# gocupi_v1_1.net
KiCad netlist of a schematic drawn in EAGLE
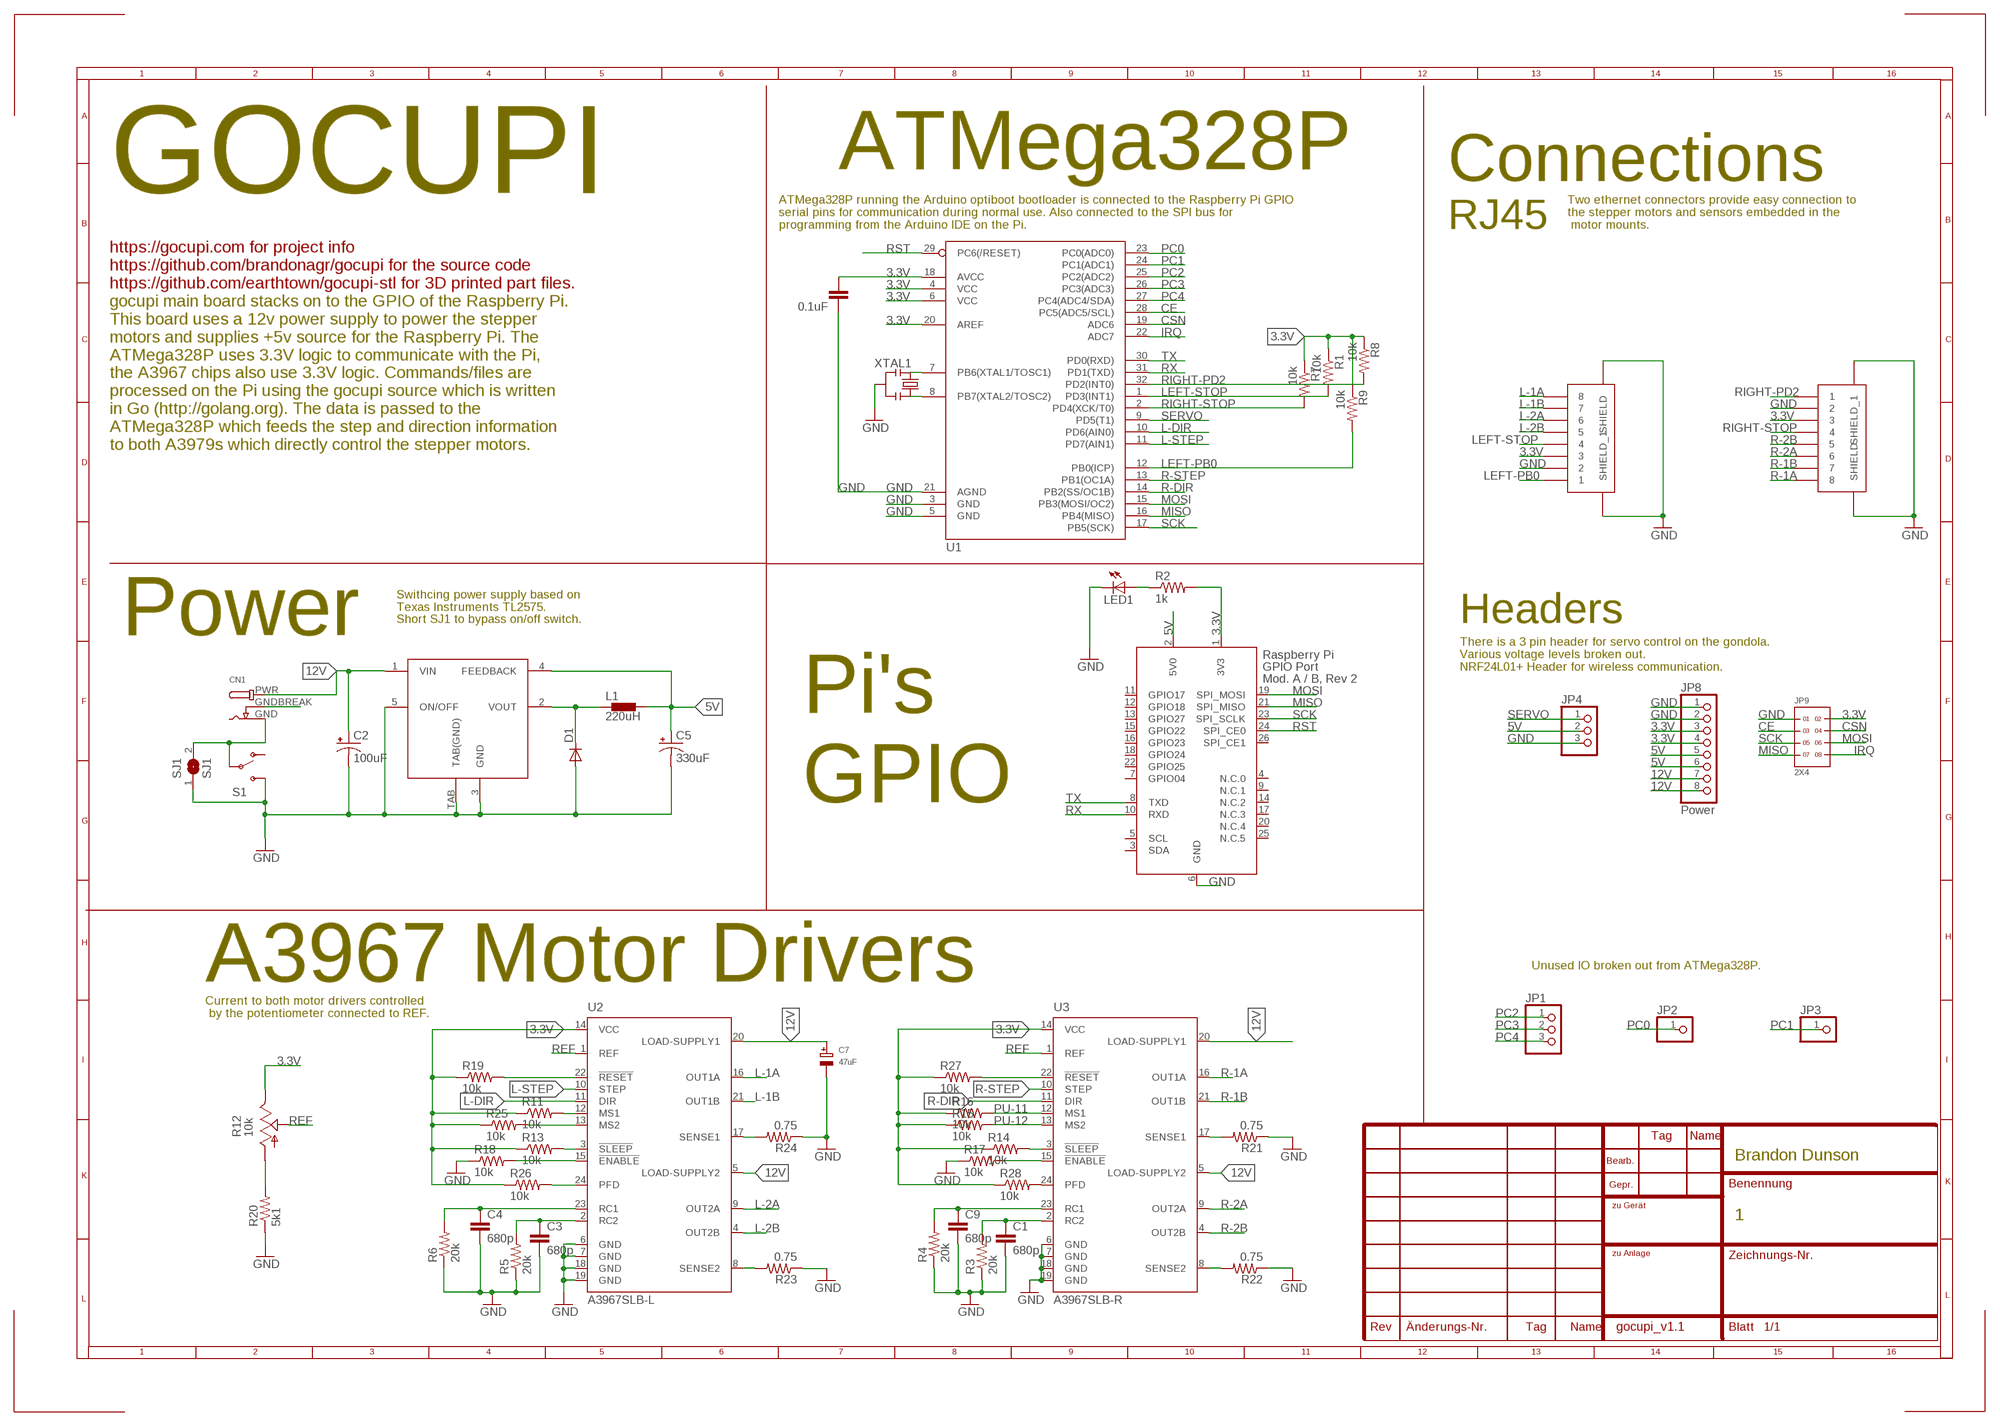
[diagram p0: schematic, sheet 1]

(export (version "E")
  (design (tool "Eeschema 10.0.6"))
  (components
    (comp (ref "C1")
      (value "680p")
      (footprint "eagle-import:0805")
      (libsource (lib "eagle-import") (part "CAP0805"))
    )
    (comp (ref "C2")
      (value "100uF")
      (footprint "eagle-import:PANASONIC_D")
      (libsource (lib "eagle-import") (part "CPOL-USD"))
    )
    (comp (ref "C3")
      (value "680p")
      (footprint "eagle-import:0805")
      (libsource (lib "eagle-import") (part "CAP0805"))
    )
    (comp (ref "C4")
      (value "680p")
      (footprint "eagle-import:0805")
      (libsource (lib "eagle-import") (part "CAP0805"))
    )
    (comp (ref "C5")
      (value "330uF")
      (footprint "eagle-import:PANASONIC_F")
      (libsource (lib "eagle-import") (part "CPOL-USF"))
    )
    (comp (ref "C7")
      (value "47uF")
      (footprint "eagle-import:PANASONIC_C")
      (libsource (lib "eagle-import") (part "CAP_ELECTROLYTICPANASONIC_C"))
    )
    (comp (ref "C8")
      (value "0.1uF")
      (footprint "eagle-import:0805")
      (libsource (lib "eagle-import") (part "CAP0805"))
    )
    (comp (ref "C9")
      (value "680p")
      (footprint "eagle-import:0805")
      (libsource (lib "eagle-import") (part "CAP0805"))
    )
    (comp (ref "CN1")
      (value "DCBARRELSMT_CORRECT")
      (footprint "eagle-import:DCJACK_2MM_SMT")
      (libsource (lib "eagle-import") (part "DCBARRELSMT_CORRECT"))
    )
    (comp (ref "D1")
      (value "DIODE-SOD-123")
      (footprint "eagle-import:SOD-123")
      (libsource (lib "eagle-import") (part "DIODE-SOD-123"))
    )
    (comp (ref "JP1")
      (value "PINHD-1X3CB")
      (footprint "eagle-import:1X03-CLEANBIG")
      (libsource (lib "eagle-import") (part "PINHD-1X3CB"))
    )
    (comp (ref "JP2")
      (value "PINHD-1X1CB")
      (footprint "eagle-import:1X01-CLEANBIG")
      (libsource (lib "eagle-import") (part "PINHD-1X1CB"))
    )
    (comp (ref "JP3")
      (value "PINHD-1X1CB")
      (footprint "eagle-import:1X01-CLEANBIG")
      (libsource (lib "eagle-import") (part "PINHD-1X1CB"))
    )
    (comp (ref "JP4")
      (value "PINHD-1X3")
      (footprint "eagle-import:1X03")
      (libsource (lib "eagle-import") (part "PINHD-1X3"))
    )
    (comp (ref "JP8")
      (value "Power")
      (footprint "eagle-import:1X08-CLEANBIG")
      (libsource (lib "eagle-import") (part "PINHD-1X8CLEANBIG"))
    )
    (comp (ref "JP9")
      (value "2X4")
      (footprint "eagle-import:2X4")
      (libsource (lib "eagle-import") (part "2X4"))
    )
    (comp (ref "L1")
      (value "220uH")
      (footprint "eagle-import:SDR1305")
      (libsource (lib "eagle-import") (part "SDR1305"))
    )
    (comp (ref "LED1")
      (value "LEDCHIPLED_0805")
      (footprint "eagle-import:CHIPLED_0805")
      (libsource (lib "eagle-import") (part "LEDCHIPLED_0805"))
    )
    (comp (ref "R1")
      (value "10k")
      (footprint "eagle-import:0805")
      (libsource (lib "eagle-import") (part "SparkFun-Resistors_RESISTOR0805-RES"))
    )
    (comp (ref "R2")
      (value "1k")
      (footprint "eagle-import:0805")
      (libsource (lib "eagle-import") (part "SparkFun-Resistors_RESISTOR0805-RES"))
    )
    (comp (ref "R3")
      (value "20k")
      (footprint "eagle-import:0805")
      (libsource (lib "eagle-import") (part "SparkFun-Resistors_RESISTOR0805-RES"))
    )
    (comp (ref "R4")
      (value "20k")
      (footprint "eagle-import:0805")
      (libsource (lib "eagle-import") (part "SparkFun-Resistors_RESISTOR0805-RES"))
    )
    (comp (ref "R5")
      (value "20k")
      (footprint "eagle-import:0805")
      (libsource (lib "eagle-import") (part "SparkFun-Resistors_RESISTOR0805-RES"))
    )
    (comp (ref "R6")
      (value "20k")
      (footprint "eagle-import:0805")
      (libsource (lib "eagle-import") (part "SparkFun-Resistors_RESISTOR0805-RES"))
    )
    (comp (ref "R7")
      (value "10k")
      (footprint "eagle-import:0805")
      (libsource (lib "eagle-import") (part "SparkFun-Resistors_RESISTOR0805-RES"))
    )
    (comp (ref "R8")
      (value "10k")
      (footprint "eagle-import:0805")
      (libsource (lib "eagle-import") (part "SparkFun-Resistors_RESISTOR0805-RES"))
    )
    (comp (ref "R9")
      (value "10k")
      (footprint "eagle-import:0805")
      (libsource (lib "eagle-import") (part "SparkFun-Resistors_RESISTOR0805-RES"))
    )
    (comp (ref "R11")
      (value "10k")
      (footprint "eagle-import:0805")
      (libsource (lib "eagle-import") (part "SparkFun-Resistors_RESISTOR0805-RES"))
    )
    (comp (ref "R12")
      (value "10k")
      (footprint "eagle-import:SM-42_43A")
      (libsource (lib "eagle-import") (part "TRIM_US-SM-42/43A"))
    )
    (comp (ref "R13")
      (value "10k")
      (footprint "eagle-import:0805")
      (libsource (lib "eagle-import") (part "SparkFun-Resistors_RESISTOR0805-RES"))
    )
    (comp (ref "R14")
      (value "10k")
      (footprint "eagle-import:0805")
      (libsource (lib "eagle-import") (part "SparkFun-Resistors_RESISTOR0805-RES"))
    )
    (comp (ref "R15")
      (value "10k")
      (footprint "eagle-import:0805")
      (libsource (lib "eagle-import") (part "SparkFun-Resistors_RESISTOR0805-RES"))
    )
    (comp (ref "R16")
      (value "10k")
      (footprint "eagle-import:0805")
      (libsource (lib "eagle-import") (part "SparkFun-Resistors_RESISTOR0805-RES"))
    )
    (comp (ref "R17")
      (value "10k")
      (footprint "eagle-import:0805")
      (libsource (lib "eagle-import") (part "SparkFun-Resistors_RESISTOR0805-RES"))
    )
    (comp (ref "R18")
      (value "10k")
      (footprint "eagle-import:0805")
      (libsource (lib "eagle-import") (part "SparkFun-Resistors_RESISTOR0805-RES"))
    )
    (comp (ref "R19")
      (value "10k")
      (footprint "eagle-import:0805")
      (libsource (lib "eagle-import") (part "SparkFun-Resistors_RESISTOR0805-RES"))
    )
    (comp (ref "R20")
      (value "5k1")
      (footprint "eagle-import:0805")
      (libsource (lib "eagle-import") (part "SparkFun-Resistors_RESISTOR0805-RES"))
    )
    (comp (ref "R21")
      (value "0.75")
      (footprint "eagle-import:0805")
      (libsource (lib "eagle-import") (part "SparkFun-Resistors_RESISTOR0805-RES"))
    )
    (comp (ref "R22")
      (value "0.75")
      (footprint "eagle-import:0805")
      (libsource (lib "eagle-import") (part "SparkFun-Resistors_RESISTOR0805-RES"))
    )
    (comp (ref "R23")
      (value "0.75")
      (footprint "eagle-import:0805")
      (libsource (lib "eagle-import") (part "SparkFun-Resistors_RESISTOR0805-RES"))
    )
    (comp (ref "R24")
      (value "0.75")
      (footprint "eagle-import:0805")
      (libsource (lib "eagle-import") (part "SparkFun-Resistors_RESISTOR0805-RES"))
    )
    (comp (ref "R25")
      (value "10k")
      (footprint "eagle-import:0805")
      (libsource (lib "eagle-import") (part "RESISTOR0805-RES"))
    )
    (comp (ref "R26")
      (value "10k")
      (footprint "eagle-import:0805")
      (libsource (lib "eagle-import") (part "SparkFun-Resistors_RESISTOR0805-RES"))
    )
    (comp (ref "R27")
      (value "10k")
      (footprint "eagle-import:0805")
      (libsource (lib "eagle-import") (part "SparkFun-Resistors_RESISTOR0805-RES"))
    )
    (comp (ref "R28")
      (value "10k")
      (footprint "eagle-import:0805")
      (libsource (lib "eagle-import") (part "SparkFun-Resistors_RESISTOR0805-RES"))
    )
    (comp (ref "RJ45-L")
      (value "RJ45_SMD")
      (footprint "eagle-import:RJ45_SMD")
      (libsource (lib "eagle-import") (part "RJ45_SMD"))
    )
    (comp (ref "RJ45-R")
      (value "RJ45_SMD")
      (footprint "eagle-import:RJ45_SMD")
      (libsource (lib "eagle-import") (part "RJ45_SMD"))
    )
    (comp (ref "S1")
      (value "SWITCH-SPST-SMD-A")
      (footprint "eagle-import:SWITCH-SPST-SMD-A")
      (libsource (lib "eagle-import") (part "SWITCH-SPST-SMD-A"))
    )
    (comp (ref "SJ1")
      (value "SJ1")
      (footprint "eagle-import:SJ")
      (libsource (lib "eagle-import") (part "SJ"))
    )
    (comp (ref "U1")
      (value "ATMEGA328_SMT")
      (footprint "eagle-import:TQFP32-08")
      (libsource (lib "eagle-import") (part "ATMEGA328_SMT"))
    )
    (comp (ref "U2")
      (value "A3967SLB-L")
      (footprint "eagle-import:SO24W")
      (fields (field (name "MF") "ALLEGRO MICROSYSTEMS, INC.") (field (name "MPN") "A3967SLB-T"))
      (libsource (lib "eagle-import") (part "A3967SLB"))
    )
    (comp (ref "U3")
      (value "A3967SLB-R")
      (footprint "eagle-import:SO24W")
      (fields (field (name "MF") "ALLEGRO MICROSYSTEMS, INC.") (field (name "MPN") "A3967SLB-T"))
      (libsource (lib "eagle-import") (part "A3967SLB"))
    )
    (comp (ref "U4")
      (value "TL2575")
      (footprint "eagle-import:TO263_5")
      (libsource (lib "eagle-import") (part "TL2575"))
    )
    (comp (ref "X1")
      (value "RASPI_BOARD_AB_E2P")
      (footprint "eagle-import:RASPI_BOARD_AB_EDGES_2DRILL_PAD")
      (libsource (lib "eagle-import") (part "RASPI_BOARD_AB_E2P"))
    )
    (comp (ref "XTAL1")
      (value "10MHz")
      (footprint "eagle-import:RESONATOR-SMD")
      (libsource (lib "eagle-import") (part "RESONATORSMD"))
    )
  )
  (nets
    (net (code "1") (name "/CE") (class "Default")
      (node (ref "JP9") (pin "3") (pinfunction "3_3") (pintype "bidirectional"))
      (node (ref "U1") (pin "28") (pinfunction "PC5(ADC5/SCL)_28") (pintype "bidirectional"))
    )
    (net (code "2") (name "/CSN") (class "Default")
      (node (ref "JP9") (pin "4") (pinfunction "4_4") (pintype "bidirectional"))
      (node (ref "U1") (pin "19") (pinfunction "ADC6_19") (pintype "bidirectional"))
    )
    (net (code "3") (name "/IRQ") (class "Default")
      (node (ref "JP9") (pin "8") (pinfunction "8_8") (pintype "bidirectional"))
      (node (ref "U1") (pin "22") (pinfunction "ADC7_22") (pintype "bidirectional"))
    )
    (net (code "4") (name "/L-1A") (class "Default")
      (node (ref "RJ45-L") (pin "P$8") (pinfunction "8_P$8") (pintype "bidirectional"))
      (node (ref "U2") (pin "16") (pinfunction "OUT1A_16") (pintype "output"))
    )
    (net (code "5") (name "/L-1B") (class "Default")
      (node (ref "RJ45-L") (pin "P$7") (pinfunction "7_P$7") (pintype "bidirectional"))
      (node (ref "U2") (pin "21") (pinfunction "OUT1B_21") (pintype "output"))
    )
    (net (code "6") (name "/L-2A") (class "Default")
      (node (ref "RJ45-L") (pin "P$6") (pinfunction "6_P$6") (pintype "bidirectional"))
      (node (ref "U2") (pin "9") (pinfunction "OUT2A_9") (pintype "output"))
    )
    (net (code "7") (name "/L-2B") (class "Default")
      (node (ref "RJ45-L") (pin "P$5") (pinfunction "5_P$5") (pintype "bidirectional"))
      (node (ref "U2") (pin "4") (pinfunction "OUT2B_4") (pintype "output"))
    )
    (net (code "8") (name "/LEFT-PB0") (class "Default")
      (node (ref "R9") (pin "2") (pinfunction "2_2") (pintype "passive"))
      (node (ref "RJ45-L") (pin "P$1") (pinfunction "1_P$1") (pintype "bidirectional"))
      (node (ref "U1") (pin "12") (pinfunction "PB0(ICP)_12") (pintype "bidirectional"))
    )
    (net (code "9") (name "/LEFT-STOP") (class "Default")
      (node (ref "R1") (pin "2") (pinfunction "2_2") (pintype "passive"))
      (node (ref "RJ45-L") (pin "P$4") (pinfunction "4_P$4") (pintype "bidirectional"))
      (node (ref "U1") (pin "1") (pinfunction "PD3(INT1)_1") (pintype "bidirectional"))
    )
    (net (code "10") (name "/MISO") (class "Default")
      (node (ref "JP9") (pin "7") (pinfunction "7_7") (pintype "bidirectional"))
      (node (ref "U1") (pin "16") (pinfunction "PB4(MISO)_16") (pintype "bidirectional"))
      (node (ref "X1") (pin "21") (pinfunction "SPI_MISO_21") (pintype "bidirectional"))
    )
    (net (code "11") (name "/MOSI") (class "Default")
      (node (ref "JP9") (pin "6") (pinfunction "6_6") (pintype "bidirectional"))
      (node (ref "U1") (pin "15") (pinfunction "PB3(MOSI/OC2)_15") (pintype "bidirectional"))
      (node (ref "X1") (pin "19") (pinfunction "SPI_MOSI_19") (pintype "bidirectional"))
    )
    (net (code "12") (name "/PC0") (class "Default")
      (node (ref "JP2") (pin "1") (pinfunction "1_1") (pintype "passive"))
      (node (ref "U1") (pin "23") (pinfunction "PC0(ADC0)_23") (pintype "bidirectional"))
    )
    (net (code "13") (name "/PC1") (class "Default")
      (node (ref "JP3") (pin "1") (pinfunction "1_1") (pintype "passive"))
      (node (ref "U1") (pin "24") (pinfunction "PC1(ADC1)_24") (pintype "bidirectional"))
    )
    (net (code "14") (name "/PC2") (class "Default")
      (node (ref "JP1") (pin "1") (pinfunction "1_1") (pintype "passive"))
      (node (ref "U1") (pin "25") (pinfunction "PC2(ADC2)_25") (pintype "bidirectional"))
    )
    (net (code "15") (name "/PC3") (class "Default")
      (node (ref "JP1") (pin "2") (pinfunction "2_2") (pintype "passive"))
      (node (ref "U1") (pin "26") (pinfunction "PC3(ADC3)_26") (pintype "bidirectional"))
    )
    (net (code "16") (name "/PC4") (class "Default")
      (node (ref "JP1") (pin "3") (pinfunction "3_3") (pintype "passive"))
      (node (ref "U1") (pin "27") (pinfunction "PC4(ADC4/SDA)_27") (pintype "bidirectional"))
    )
    (net (code "17") (name "/PU-11") (class "Default")
      (node (ref "R16") (pin "2") (pinfunction "2_2") (pintype "passive"))
      (node (ref "U3") (pin "12") (pinfunction "MS1_12") (pintype "input"))
    )
    (net (code "18") (name "/PU-12") (class "Default")
      (node (ref "R15") (pin "2") (pinfunction "2_2") (pintype "passive"))
      (node (ref "U3") (pin "13") (pinfunction "MS2_13") (pintype "input"))
    )
    (net (code "19") (name "/R-1A") (class "Default")
      (node (ref "RJ45-R") (pin "P$8") (pinfunction "8_P$8") (pintype "bidirectional"))
      (node (ref "U3") (pin "16") (pinfunction "OUT1A_16") (pintype "output"))
    )
    (net (code "20") (name "/R-1B") (class "Default")
      (node (ref "RJ45-R") (pin "P$7") (pinfunction "7_P$7") (pintype "bidirectional"))
      (node (ref "U3") (pin "21") (pinfunction "OUT1B_21") (pintype "output"))
    )
    (net (code "21") (name "/R-2A") (class "Default")
      (node (ref "RJ45-R") (pin "P$6") (pinfunction "6_P$6") (pintype "bidirectional"))
      (node (ref "U3") (pin "9") (pinfunction "OUT2A_9") (pintype "output"))
    )
    (net (code "22") (name "/R-2B") (class "Default")
      (node (ref "RJ45-R") (pin "P$5") (pinfunction "5_P$5") (pintype "bidirectional"))
      (node (ref "U3") (pin "4") (pinfunction "OUT2B_4") (pintype "output"))
    )
    (net (code "23") (name "/REF") (class "Default")
      (node (ref "R12") (pin "2") (pinfunction "S_2") (pintype "passive"))
      (node (ref "U2") (pin "1") (pinfunction "REF_1") (pintype "input"))
      (node (ref "U3") (pin "1") (pinfunction "REF_1") (pintype "input"))
    )
    (net (code "24") (name "/RIGHT-PD2") (class "Default")
      (node (ref "R8") (pin "2") (pinfunction "2_2") (pintype "passive"))
      (node (ref "RJ45-R") (pin "P$1") (pinfunction "1_P$1") (pintype "bidirectional"))
      (node (ref "U1") (pin "32") (pinfunction "PD2(INT0)_32") (pintype "bidirectional"))
    )
    (net (code "25") (name "/RIGHT-STOP") (class "Default")
      (node (ref "R7") (pin "2") (pinfunction "2_2") (pintype "passive"))
      (node (ref "RJ45-R") (pin "P$4") (pinfunction "4_P$4") (pintype "bidirectional"))
      (node (ref "U1") (pin "2") (pinfunction "PD4(XCK/T0)_2") (pintype "bidirectional"))
    )
    (net (code "26") (name "/RST") (class "Default")
      (node (ref "U1") (pin "29") (pinfunction "PC6(/RESET)_29") (pintype "bidirectional"))
      (node (ref "X1") (pin "24") (pinfunction "SPI_CE0_24") (pintype "bidirectional"))
    )
    (net (code "27") (name "/RX") (class "Default")
      (node (ref "U1") (pin "31") (pinfunction "PD1(TXD)_31") (pintype "bidirectional"))
      (node (ref "X1") (pin "10") (pinfunction "RXD_10") (pintype "bidirectional"))
    )
    (net (code "28") (name "/SCK") (class "Default")
      (node (ref "JP9") (pin "5") (pinfunction "5_5") (pintype "bidirectional"))
      (node (ref "U1") (pin "17") (pinfunction "PB5(SCK)_17") (pintype "bidirectional"))
      (node (ref "X1") (pin "23") (pinfunction "SPI_SCLK_23") (pintype "bidirectional"))
    )
    (net (code "29") (name "/SERVO") (class "Default")
      (node (ref "JP4") (pin "1") (pinfunction "1_1") (pintype "passive"))
      (node (ref "U1") (pin "9") (pinfunction "PD5(T1)_9") (pintype "bidirectional"))
    )
    (net (code "30") (name "/TX") (class "Default")
      (node (ref "U1") (pin "30") (pinfunction "PD0(RXD)_30") (pintype "bidirectional"))
      (node (ref "X1") (pin "8") (pinfunction "TXD_8") (pintype "bidirectional"))
    )
    (net (code "31") (name "3.3V") (class "Default")
      (node (ref "C8") (pin "1") (pinfunction "1_1") (pintype "passive"))
      (node (ref "JP8") (pin "3") (pinfunction "3_3") (pintype "passive"))
      (node (ref "JP8") (pin "4") (pinfunction "4_4") (pintype "passive"))
      (node (ref "JP9") (pin "2") (pinfunction "2_2") (pintype "bidirectional"))
      (node (ref "R1") (pin "1") (pinfunction "1_1") (pintype "passive"))
      (node (ref "R11") (pin "1") (pinfunction "1_1") (pintype "passive"))
      (node (ref "R12") (pin "3") (pinfunction "E_3") (pintype "passive"))
      (node (ref "R13") (pin "1") (pinfunction "1_1") (pintype "passive"))
      (node (ref "R14") (pin "1") (pinfunction "1_1") (pintype "passive"))
      (node (ref "R15") (pin "1") (pinfunction "1_1") (pintype "passive"))
      (node (ref "R16") (pin "1") (pinfunction "1_1") (pintype "passive"))
      (node (ref "R19") (pin "1") (pinfunction "1_1") (pintype "passive"))
      (node (ref "R2") (pin "2") (pinfunction "2_2") (pintype "passive"))
      (node (ref "R25") (pin "1") (pinfunction "1_1") (pintype "passive"))
      (node (ref "R26") (pin "1") (pinfunction "1_1") (pintype "passive"))
      (node (ref "R27") (pin "1") (pinfunction "1_1") (pintype "passive"))
      (node (ref "R28") (pin "1") (pinfunction "1_1") (pintype "passive"))
      (node (ref "R7") (pin "1") (pinfunction "1_1") (pintype "passive"))
      (node (ref "R8") (pin "1") (pinfunction "1_1") (pintype "passive"))
      (node (ref "R9") (pin "1") (pinfunction "1_1") (pintype "passive"))
      (node (ref "RJ45-L") (pin "P$3") (pinfunction "3_P$3") (pintype "bidirectional"))
      (node (ref "RJ45-R") (pin "P$3") (pinfunction "3_P$3") (pintype "bidirectional"))
      (node (ref "U1") (pin "18") (pinfunction "AVCC_18") (pintype "bidirectional"))
      (node (ref "U1") (pin "20") (pinfunction "AREF_20") (pintype "bidirectional"))
      (node (ref "U1") (pin "4") (pinfunction "VCC_4") (pintype "bidirectional"))
      (node (ref "U1") (pin "6") (pinfunction "VCC_6") (pintype "bidirectional"))
      (node (ref "U2") (pin "14") (pinfunction "VCC_14") (pintype "power_in"))
      (node (ref "U3") (pin "14") (pinfunction "VCC_14") (pintype "power_in"))
      (node (ref "X1") (pin "1") (pinfunction "3V3_1") (pintype "power_in"))
    )
    (net (code "32") (name "5V") (class "Default")
      (node (ref "C5") (pin "+") (pinfunction "+_+") (pintype "passive"))
      (node (ref "JP4") (pin "2") (pinfunction "2_2") (pintype "passive"))
      (node (ref "JP8") (pin "5") (pinfunction "5_5") (pintype "passive"))
      (node (ref "JP8") (pin "6") (pinfunction "6_6") (pintype "passive"))
      (node (ref "L1") (pin "P$2") (pinfunction "2_P$2") (pintype "passive"))
      (node (ref "U4") (pin "4") (pinfunction "FEEDBACK_4") (pintype "input"))
      (node (ref "X1") (pin "2") (pinfunction "5V0_2") (pintype "power_in"))
    )
    (net (code "33") (name "12V") (class "Default")
      (node (ref "C2") (pin "+") (pinfunction "+_+") (pintype "passive"))
      (node (ref "C7") (pin "+") (pinfunction "+_+") (pintype "passive"))
      (node (ref "CN1") (pin "PWR") (pinfunction "PWR_PWR") (pintype "power_in"))
      (node (ref "JP8") (pin "7") (pinfunction "7_7") (pintype "passive"))
      (node (ref "JP8") (pin "8") (pinfunction "8_8") (pintype "passive"))
      (node (ref "U2") (pin "20") (pinfunction "LOAD-SUPPLY1_20") (pintype "input"))
      (node (ref "U2") (pin "5") (pinfunction "LOAD-SUPPLY2_5") (pintype "input"))
      (node (ref "U3") (pin "20") (pinfunction "LOAD-SUPPLY1_20") (pintype "input"))
      (node (ref "U3") (pin "5") (pinfunction "LOAD-SUPPLY2_5") (pintype "input"))
      (node (ref "U4") (pin "1") (pinfunction "VIN_1") (pintype "input"))
    )
    (net (code "34") (name "GND") (class "Default")
      (node (ref "C1") (pin "2") (pinfunction "2_2") (pintype "passive"))
      (node (ref "C2") (pin "-") (pinfunction "-_-") (pintype "passive"))
      (node (ref "C3") (pin "2") (pinfunction "2_2") (pintype "passive"))
      (node (ref "C4") (pin "2") (pinfunction "2_2") (pintype "passive"))
      (node (ref "C5") (pin "-") (pinfunction "-_-") (pintype "passive"))
      (node (ref "C7") (pin "-") (pinfunction "-_-") (pintype "passive"))
      (node (ref "C8") (pin "2") (pinfunction "2_2") (pintype "passive"))
      (node (ref "C9") (pin "2") (pinfunction "2_2") (pintype "passive"))
      (node (ref "D1") (pin "A") (pinfunction "A_A") (pintype "passive"))
      (node (ref "JP4") (pin "3") (pinfunction "3_3") (pintype "passive"))
      (node (ref "JP8") (pin "1") (pinfunction "1_1") (pintype "passive"))
      (node (ref "JP8") (pin "2") (pinfunction "2_2") (pintype "passive"))
      (node (ref "JP9") (pin "1") (pinfunction "1_1") (pintype "bidirectional"))
      (node (ref "LED1") (pin "C") (pinfunction "C_C") (pintype "passive"))
      (node (ref "R17") (pin "1") (pinfunction "1_1") (pintype "passive"))
      (node (ref "R18") (pin "1") (pinfunction "1_1") (pintype "passive"))
      (node (ref "R20") (pin "1") (pinfunction "1_1") (pintype "passive"))
      (node (ref "R21") (pin "1") (pinfunction "1_1") (pintype "passive"))
      (node (ref "R22") (pin "1") (pinfunction "1_1") (pintype "passive"))
      (node (ref "R23") (pin "1") (pinfunction "1_1") (pintype "passive"))
      (node (ref "R24") (pin "1") (pinfunction "1_1") (pintype "passive"))
      (node (ref "R3") (pin "1") (pinfunction "1_1") (pintype "passive"))
      (node (ref "R4") (pin "1") (pinfunction "1_1") (pintype "passive"))
      (node (ref "R5") (pin "1") (pinfunction "1_1") (pintype "passive"))
      (node (ref "R6") (pin "1") (pinfunction "1_1") (pintype "passive"))
      (node (ref "RJ45-L") (pin "P$2") (pinfunction "2_P$2") (pintype "bidirectional"))
      (node (ref "RJ45-L") (pin "P$SHIELD") (pinfunction "SHIELD_P$SHIELD") (pintype "bidirectional"))
      (node (ref "RJ45-L") (pin "P$SHIELD_1") (pinfunction "SHIELD_1_P$SHIELD_1") (pintype "bidirectional"))
      (node (ref "RJ45-R") (pin "P$2") (pinfunction "2_P$2") (pintype "bidirectional"))
      (node (ref "RJ45-R") (pin "P$SHIELD") (pinfunction "SHIELD_P$SHIELD") (pintype "bidirectional"))
      (node (ref "RJ45-R") (pin "P$SHIELD_1") (pinfunction "SHIELD_1_P$SHIELD_1") (pintype "bidirectional"))
      (node (ref "S1") (pin "3") (pinfunction "S_3") (pintype "passive"))
      (node (ref "SJ1") (pin "1") (pinfunction "1_1") (pintype "passive"))
      (node (ref "U1") (pin "21") (pinfunction "AGND_21") (pintype "bidirectional"))
      (node (ref "U1") (pin "3") (pinfunction "GND_3") (pintype "bidirectional"))
      (node (ref "U1") (pin "5") (pinfunction "GND_5") (pintype "bidirectional"))
      (node (ref "U2") (pin "18") (pinfunction "GND_18") (pintype "power_in"))
      (node (ref "U2") (pin "19") (pinfunction "GND_19") (pintype "power_in"))
      (node (ref "U2") (pin "6") (pinfunction "GND_6") (pintype "power_in"))
      (node (ref "U2") (pin "7") (pinfunction "GND_7") (pintype "power_in"))
      (node (ref "U3") (pin "18") (pinfunction "GND_18") (pintype "power_in"))
      (node (ref "U3") (pin "19") (pinfunction "GND_19") (pintype "power_in"))
      (node (ref "U3") (pin "6") (pinfunction "GND_6") (pintype "power_in"))
      (node (ref "U3") (pin "7") (pinfunction "GND_7") (pintype "power_in"))
      (node (ref "U4") (pin "3") (pinfunction "GND_3") (pintype "power_in"))
      (node (ref "U4") (pin "5") (pinfunction "ON/OFF_5") (pintype "bidirectional"))
      (node (ref "U4") (pin "TAB") (pinfunction "TAB(GND)_TAB") (pintype "power_in"))
      (node (ref "X1") (pin "6") (pinfunction "GND_6") (pintype "power_in"))
      (node (ref "XTAL1") (pin "2") (pinfunction "2_2") (pintype "passive"))
    )
    (net (code "35") (name "L-DIR") (class "Default")
      (node (ref "U1") (pin "10") (pinfunction "PD6(AIN0)_10") (pintype "bidirectional"))
      (node (ref "U2") (pin "11") (pinfunction "DIR_11") (pintype "input"))
    )
    (net (code "36") (name "L-STEP") (class "Default")
      (node (ref "U1") (pin "11") (pinfunction "PD7(AIN1)_11") (pintype "bidirectional"))
      (node (ref "U2") (pin "10") (pinfunction "STEP_10") (pintype "input"))
    )
    (net (code "37") (name "Net-(L1-1)") (class "Default")
      (node (ref "D1") (pin "C") (pinfunction "C_C") (pintype "passive"))
      (node (ref "L1") (pin "P$1") (pinfunction "1_P$1") (pintype "passive"))
      (node (ref "U4") (pin "2") (pinfunction "VOUT_2") (pintype "output"))
    )
    (net (code "38") (name "Net-(LED1-PadA)") (class "Default")
      (node (ref "LED1") (pin "A") (pinfunction "A_A") (pintype "passive"))
      (node (ref "R2") (pin "1") (pinfunction "1_1") (pintype "passive"))
    )
    (net (code "39") (name "Net-(R12-A)") (class "Default")
      (node (ref "R12") (pin "1") (pinfunction "A_1") (pintype "passive"))
      (node (ref "R20") (pin "2") (pinfunction "2_2") (pintype "passive"))
    )
    (net (code "40") (name "Net-(S1-P)") (class "Default")
      (node (ref "CN1") (pin "GND") (pinfunction "GND_GND") (pintype "power_in"))
      (node (ref "S1") (pin "2") (pinfunction "P_2") (pintype "passive"))
      (node (ref "SJ1") (pin "2") (pinfunction "2_2") (pintype "passive"))
    )
    (net (code "41") (name "Net-(U1-PB6(XTAL1{slash}TOSC1))") (class "Default")
      (node (ref "U1") (pin "7") (pinfunction "PB6(XTAL1/TOSC1)_7") (pintype "bidirectional"))
      (node (ref "XTAL1") (pin "1") (pinfunction "1_1") (pintype "passive"))
    )
    (net (code "42") (name "Net-(U1-PB7(XTAL2{slash}TOSC2))") (class "Default")
      (node (ref "U1") (pin "8") (pinfunction "PB7(XTAL2/TOSC2)_8") (pintype "bidirectional"))
      (node (ref "XTAL1") (pin "3") (pinfunction "3_3") (pintype "passive"))
    )
    (net (code "43") (name "Net-(U2-MS1)") (class "Default")
      (node (ref "R11") (pin "2") (pinfunction "2_2") (pintype "passive"))
      (node (ref "U2") (pin "12") (pinfunction "MS1_12") (pintype "input"))
    )
    (net (code "44") (name "Net-(U2-MS2)") (class "Default")
      (node (ref "R25") (pin "2") (pinfunction "2_2") (pintype "passive"))
      (node (ref "U2") (pin "13") (pinfunction "MS2_13") (pintype "input"))
    )
    (net (code "45") (name "Net-(U2-PFD)") (class "Default")
      (node (ref "R26") (pin "2") (pinfunction "2_2") (pintype "passive"))
      (node (ref "U2") (pin "24") (pinfunction "PFD_24") (pintype "input"))
    )
    (net (code "46") (name "Net-(U2-RC1)") (class "Default")
      (node (ref "C4") (pin "1") (pinfunction "1_1") (pintype "passive"))
      (node (ref "R6") (pin "2") (pinfunction "2_2") (pintype "passive"))
      (node (ref "U2") (pin "23") (pinfunction "RC1_23") (pintype "input"))
    )
    (net (code "47") (name "Net-(U2-RC2)") (class "Default")
      (node (ref "C3") (pin "1") (pinfunction "1_1") (pintype "passive"))
      (node (ref "R5") (pin "2") (pinfunction "2_2") (pintype "passive"))
      (node (ref "U2") (pin "2") (pinfunction "RC2_2") (pintype "input"))
    )
    (net (code "48") (name "Net-(U2-SENSE1)") (class "Default")
      (node (ref "R24") (pin "2") (pinfunction "2_2") (pintype "passive"))
      (node (ref "U2") (pin "17") (pinfunction "SENSE1_17") (pintype "input"))
    )
    (net (code "49") (name "Net-(U2-SENSE2)") (class "Default")
      (node (ref "R23") (pin "2") (pinfunction "2_2") (pintype "passive"))
      (node (ref "U2") (pin "8") (pinfunction "SENSE2_8") (pintype "input"))
    )
    (net (code "50") (name "Net-(U2-~{ENABLE})") (class "Default")
      (node (ref "R18") (pin "2") (pinfunction "2_2") (pintype "passive"))
      (node (ref "U2") (pin "15") (pinfunction "~{ENABLE}_15") (pintype "input"))
    )
    (net (code "51") (name "Net-(U2-~{RESET})") (class "Default")
      (node (ref "R19") (pin "2") (pinfunction "2_2") (pintype "passive"))
      (node (ref "U2") (pin "22") (pinfunction "~{RESET}_22") (pintype "input"))
    )
    (net (code "52") (name "Net-(U2-~{SLEEP})") (class "Default")
      (node (ref "R13") (pin "2") (pinfunction "2_2") (pintype "passive"))
      (node (ref "U2") (pin "3") (pinfunction "~{SLEEP}_3") (pintype "input"))
    )
    (net (code "53") (name "Net-(U3-PFD)") (class "Default")
      (node (ref "R28") (pin "2") (pinfunction "2_2") (pintype "passive"))
      (node (ref "U3") (pin "24") (pinfunction "PFD_24") (pintype "input"))
    )
    (net (code "54") (name "Net-(U3-RC1)") (class "Default")
      (node (ref "C9") (pin "1") (pinfunction "1_1") (pintype "passive"))
      (node (ref "R4") (pin "2") (pinfunction "2_2") (pintype "passive"))
      (node (ref "U3") (pin "23") (pinfunction "RC1_23") (pintype "input"))
    )
    (net (code "55") (name "Net-(U3-RC2)") (class "Default")
      (node (ref "C1") (pin "1") (pinfunction "1_1") (pintype "passive"))
      (node (ref "R3") (pin "2") (pinfunction "2_2") (pintype "passive"))
      (node (ref "U3") (pin "2") (pinfunction "RC2_2") (pintype "input"))
    )
    (net (code "56") (name "Net-(U3-SENSE1)") (class "Default")
      (node (ref "R21") (pin "2") (pinfunction "2_2") (pintype "passive"))
      (node (ref "U3") (pin "17") (pinfunction "SENSE1_17") (pintype "input"))
    )
    (net (code "57") (name "Net-(U3-SENSE2)") (class "Default")
      (node (ref "R22") (pin "2") (pinfunction "2_2") (pintype "passive"))
      (node (ref "U3") (pin "8") (pinfunction "SENSE2_8") (pintype "input"))
    )
    (net (code "58") (name "Net-(U3-~{ENABLE})") (class "Default")
      (node (ref "R17") (pin "2") (pinfunction "2_2") (pintype "passive"))
      (node (ref "U3") (pin "15") (pinfunction "~{ENABLE}_15") (pintype "input"))
    )
    (net (code "59") (name "Net-(U3-~{RESET})") (class "Default")
      (node (ref "R27") (pin "2") (pinfunction "2_2") (pintype "passive"))
      (node (ref "U3") (pin "22") (pinfunction "~{RESET}_22") (pintype "input"))
    )
    (net (code "60") (name "Net-(U3-~{SLEEP})") (class "Default")
      (node (ref "R14") (pin "2") (pinfunction "2_2") (pintype "passive"))
      (node (ref "U3") (pin "3") (pinfunction "~{SLEEP}_3") (pintype "input"))
    )
    (net (code "61") (name "R-DIR") (class "Default")
      (node (ref "U1") (pin "14") (pinfunction "PB2(SS/OC1B)_14") (pintype "bidirectional"))
      (node (ref "U3") (pin "11") (pinfunction "DIR_11") (pintype "input"))
    )
    (net (code "62") (name "R-STEP") (class "Default")
      (node (ref "U1") (pin "13") (pinfunction "PB1(OC1A)_13") (pintype "bidirectional"))
      (node (ref "U3") (pin "10") (pinfunction "STEP_10") (pintype "input"))
    )
    (net (code "63") (name "unconnected-(CN1-PadGNDBREAK)") (class "Default")
      (node (ref "CN1") (pin "GNDBREAK") (pinfunction "GNDBREAK_GNDBREAK") (pintype "power_in"))
    )
    (net (code "64") (name "unconnected-(S1-O-Pad1)") (class "Default")
      (node (ref "S1") (pin "1") (pinfunction "O_1") (pintype "passive"))
    )
    (net (code "65") (name "unconnected-(X1-GPIO04-Pad7)") (class "Default")
      (node (ref "X1") (pin "7") (pinfunction "GPIO04_7") (pintype "bidirectional"))
    )
    (net (code "66") (name "unconnected-(X1-GPIO17-Pad11)") (class "Default")
      (node (ref "X1") (pin "11") (pinfunction "GPIO17_11") (pintype "bidirectional"))
    )
    (net (code "67") (name "unconnected-(X1-GPIO18-Pad12)") (class "Default")
      (node (ref "X1") (pin "12") (pinfunction "GPIO18_12") (pintype "bidirectional"))
    )
    (net (code "68") (name "unconnected-(X1-GPIO22-Pad15)") (class "Default")
      (node (ref "X1") (pin "15") (pinfunction "GPIO22_15") (pintype "bidirectional"))
    )
    (net (code "69") (name "unconnected-(X1-GPIO23-Pad16)") (class "Default")
      (node (ref "X1") (pin "16") (pinfunction "GPIO23_16") (pintype "bidirectional"))
    )
    (net (code "70") (name "unconnected-(X1-GPIO24-Pad18)") (class "Default")
      (node (ref "X1") (pin "18") (pinfunction "GPIO24_18") (pintype "bidirectional"))
    )
    (net (code "71") (name "unconnected-(X1-GPIO25-Pad22)") (class "Default")
      (node (ref "X1") (pin "22") (pinfunction "GPIO25_22") (pintype "bidirectional"))
    )
    (net (code "72") (name "unconnected-(X1-GPIO27-Pad13)") (class "Default")
      (node (ref "X1") (pin "13") (pinfunction "GPIO27_13") (pintype "bidirectional"))
    )
    (net (code "73") (name "unconnected-(X1-N.C.0-Pad4)") (class "Default")
      (node (ref "X1") (pin "4") (pinfunction "N.C.0_4") (pintype "no_connect"))
    )
    (net (code "74") (name "unconnected-(X1-N.C.1-Pad9)") (class "Default")
      (node (ref "X1") (pin "9") (pinfunction "N.C.1_9") (pintype "no_connect"))
    )
    (net (code "75") (name "unconnected-(X1-N.C.2-Pad14)") (class "Default")
      (node (ref "X1") (pin "14") (pinfunction "N.C.2_14") (pintype "no_connect"))
    )
    (net (code "76") (name "unconnected-(X1-N.C.3-Pad17)") (class "Default")
      (node (ref "X1") (pin "17") (pinfunction "N.C.3_17") (pintype "no_connect"))
    )
    (net (code "77") (name "unconnected-(X1-N.C.4-Pad20)") (class "Default")
      (node (ref "X1") (pin "20") (pinfunction "N.C.4_20") (pintype "no_connect"))
    )
    (net (code "78") (name "unconnected-(X1-N.C.5-Pad25)") (class "Default")
      (node (ref "X1") (pin "25") (pinfunction "N.C.5_25") (pintype "no_connect"))
    )
    (net (code "79") (name "unconnected-(X1-SCL-Pad5)") (class "Default")
      (node (ref "X1") (pin "5") (pinfunction "SCL_5") (pintype "bidirectional"))
    )
    (net (code "80") (name "unconnected-(X1-SDA-Pad3)") (class "Default")
      (node (ref "X1") (pin "3") (pinfunction "SDA_3") (pintype "bidirectional"))
    )
    (net (code "81") (name "unconnected-(X1-SPI_CE1-Pad26)") (class "Default")
      (node (ref "X1") (pin "26") (pinfunction "SPI_CE1_26") (pintype "bidirectional"))
    )
  )
)
